# smd_preamp_with_TALL_jacks.net
KiCad netlist of a schematic drawn in EAGLE
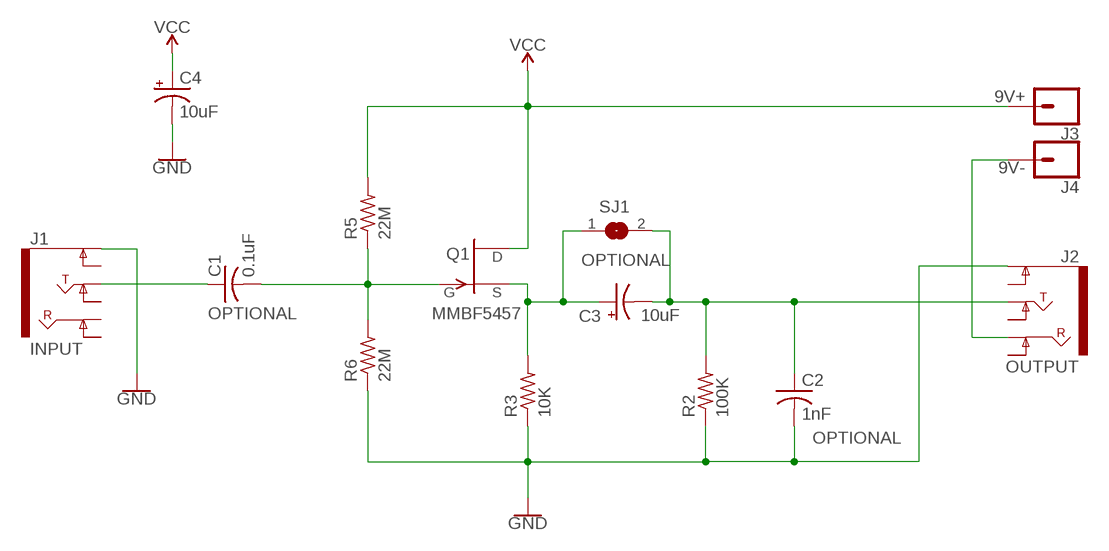
[diagram p0: schematic, sheet 1]

(export (version "E")
  (design (tool "Eeschema 10.0.6"))
  (components
    (comp (ref "C1")
      (value "0.1uF")
      (footprint "eagle-import:C0805")
      (libsource (lib "eagle-import") (part "C-USC0805"))
    )
    (comp (ref "C2")
      (value "1nF")
      (footprint "eagle-import:C0805")
      (libsource (lib "eagle-import") (part "C-USC0805"))
    )
    (comp (ref "C3")
      (value "10uF")
      (footprint "eagle-import:732-8411-1-ND_SMD")
      (libsource (lib "eagle-import") (part "732-8411-1-ND"))
    )
    (comp (ref "C4")
      (value "10uF")
      (footprint "eagle-import:732-8411-1-ND_SMD")
      (libsource (lib "eagle-import") (part "732-8411-1-ND"))
    )
    (comp (ref "J1")
      (value "INPUT")
      (footprint "eagle-import:CLIFF_AUDIO_JACK_0.25__TRS_PTH_RA")
      (libsource (lib "eagle-import") (part "CLIFF_.25{dblquote}_TRS_JACK"))
    )
    (comp (ref "J2")
      (value "OUTPUT")
      (footprint "eagle-import:CLIFF_AUDIO_JACK_0.25__TRS_PTH_RA")
      (libsource (lib "eagle-import") (part "CLIFF_.25{dblquote}_TRS_JACK"))
    )
    (comp (ref "J3")
      (value "9V+")
      (footprint "eagle-import:1X01")
      (libsource (lib "eagle-import") (part "CONN_01"))
    )
    (comp (ref "J4")
      (value "9V-")
      (footprint "eagle-import:1X01")
      (libsource (lib "eagle-import") (part "CONN_01"))
    )
    (comp (ref "Q1")
      (value "MMBF5457")
      (footprint "eagle-import:SOT23")
      (libsource (lib "eagle-import") (part "?548SST4"))
    )
    (comp (ref "R2")
      (value "100K")
      (footprint "eagle-import:R0805")
      (libsource (lib "eagle-import") (part "R-US_R0805"))
    )
    (comp (ref "R3")
      (value "10K")
      (footprint "eagle-import:R0805")
      (libsource (lib "eagle-import") (part "R-US_R0805"))
    )
    (comp (ref "R5")
      (value "22M")
      (footprint "eagle-import:R0805")
      (libsource (lib "eagle-import") (part "R-US_R0805"))
    )
    (comp (ref "R6")
      (value "22M")
      (footprint "eagle-import:R0805")
      (libsource (lib "eagle-import") (part "R-US_R0805"))
    )
    (comp (ref "SJ1") (value "SJ") (footprint "eagle-import:SJ") (libsource (lib "eagle-import") (part "SJ")))
  )
  (nets
    (net (code "1") (name "GND") (class "Default")
      (node (ref "C2") (pin "2") (pinfunction "2_2") (pintype "passive"))
      (node (ref "C4") (pin "-") (pinfunction "-_-") (pintype "passive"))
      (node (ref "J1") (pin "SLEEVE") (pinfunction "EARTH_SLEEVE") (pintype "bidirectional"))
      (node (ref "J2") (pin "SLEEVE") (pinfunction "EARTH_SLEEVE") (pintype "bidirectional"))
      (node (ref "R2") (pin "1") (pinfunction "1_1") (pintype "passive"))
      (node (ref "R3") (pin "1") (pinfunction "1_1") (pintype "passive"))
      (node (ref "R6") (pin "1") (pinfunction "1_1") (pintype "passive"))
    )
    (net (code "2") (name "Net-(C1-Pad1)") (class "Default")
      (node (ref "C1") (pin "1") (pinfunction "1_1") (pintype "passive"))
      (node (ref "J1") (pin "TIP") (pinfunction "TIP_TIP") (pintype "bidirectional"))
    )
    (net (code "3") (name "Net-(C2-Pad1)") (class "Default")
      (node (ref "C2") (pin "1") (pinfunction "1_1") (pintype "passive"))
      (node (ref "C3") (pin "-") (pinfunction "-_-") (pintype "passive"))
      (node (ref "J2") (pin "TIP") (pinfunction "TIP_TIP") (pintype "bidirectional"))
      (node (ref "R2") (pin "2") (pinfunction "2_2") (pintype "passive"))
      (node (ref "SJ1") (pin "2") (pinfunction "2_2") (pintype "passive"))
    )
    (net (code "4") (name "Net-(J2-PadRING)") (class "Default")
      (node (ref "J2") (pin "RING") (pinfunction "RING_RING") (pintype "bidirectional"))
      (node (ref "J4") (pin "1") (pinfunction "1_1") (pintype "passive"))
    )
    (net (code "5") (name "Net-(Q1-G)") (class "Default")
      (node (ref "C1") (pin "2") (pinfunction "2_2") (pintype "passive"))
      (node (ref "Q1") (pin "3") (pinfunction "G_3") (pintype "passive"))
      (node (ref "R5") (pin "1") (pinfunction "1_1") (pintype "passive"))
      (node (ref "R6") (pin "2") (pinfunction "2_2") (pintype "passive"))
    )
    (net (code "6") (name "Net-(Q1-S)") (class "Default")
      (node (ref "C3") (pin "+") (pinfunction "+_+") (pintype "passive"))
      (node (ref "Q1") (pin "2") (pinfunction "S_2") (pintype "passive"))
      (node (ref "R3") (pin "2") (pinfunction "2_2") (pintype "passive"))
      (node (ref "SJ1") (pin "1") (pinfunction "1_1") (pintype "passive"))
    )
    (net (code "7") (name "VCC") (class "Default")
      (node (ref "C4") (pin "+") (pinfunction "+_+") (pintype "passive"))
      (node (ref "J3") (pin "1") (pinfunction "1_1") (pintype "passive"))
      (node (ref "Q1") (pin "1") (pinfunction "D_1") (pintype "passive"))
      (node (ref "R5") (pin "2") (pinfunction "2_2") (pintype "passive"))
    )
    (net (code "8") (name "unconnected-(J1-EARTH-NORM-PadSLEEVE-NORM)") (class "Default")
      (node (ref "J1") (pin "SLEEVE-NORM") (pinfunction "EARTH-NORM_SLEEVE-NORM") (pintype "bidirectional"))
    )
    (net (code "9") (name "unconnected-(J1-PadRING)") (class "Default")
      (node (ref "J1") (pin "RING") (pinfunction "RING_RING") (pintype "bidirectional"))
    )
    (net (code "10") (name "unconnected-(J1-PadRING-NORM)") (class "Default")
      (node (ref "J1") (pin "RING-NORM") (pinfunction "RING-NORM_RING-NORM") (pintype "bidirectional"))
    )
    (net (code "11") (name "unconnected-(J1-PadTIP-NORM)") (class "Default")
      (node (ref "J1") (pin "TIP-NORM") (pinfunction "TIP-NORM_TIP-NORM") (pintype "bidirectional"))
    )
    (net (code "12") (name "unconnected-(J2-EARTH-NORM-PadSLEEVE-NORM)") (class "Default")
      (node (ref "J2") (pin "SLEEVE-NORM") (pinfunction "EARTH-NORM_SLEEVE-NORM") (pintype "bidirectional"))
    )
    (net (code "13") (name "unconnected-(J2-PadRING-NORM)") (class "Default")
      (node (ref "J2") (pin "RING-NORM") (pinfunction "RING-NORM_RING-NORM") (pintype "bidirectional"))
    )
    (net (code "14") (name "unconnected-(J2-PadTIP-NORM)") (class "Default")
      (node (ref "J2") (pin "TIP-NORM") (pinfunction "TIP-NORM_TIP-NORM") (pintype "bidirectional"))
    )
  )
)
